# MCPEmulate0.net
KiCad netlist of a schematic drawn in Altium Designer
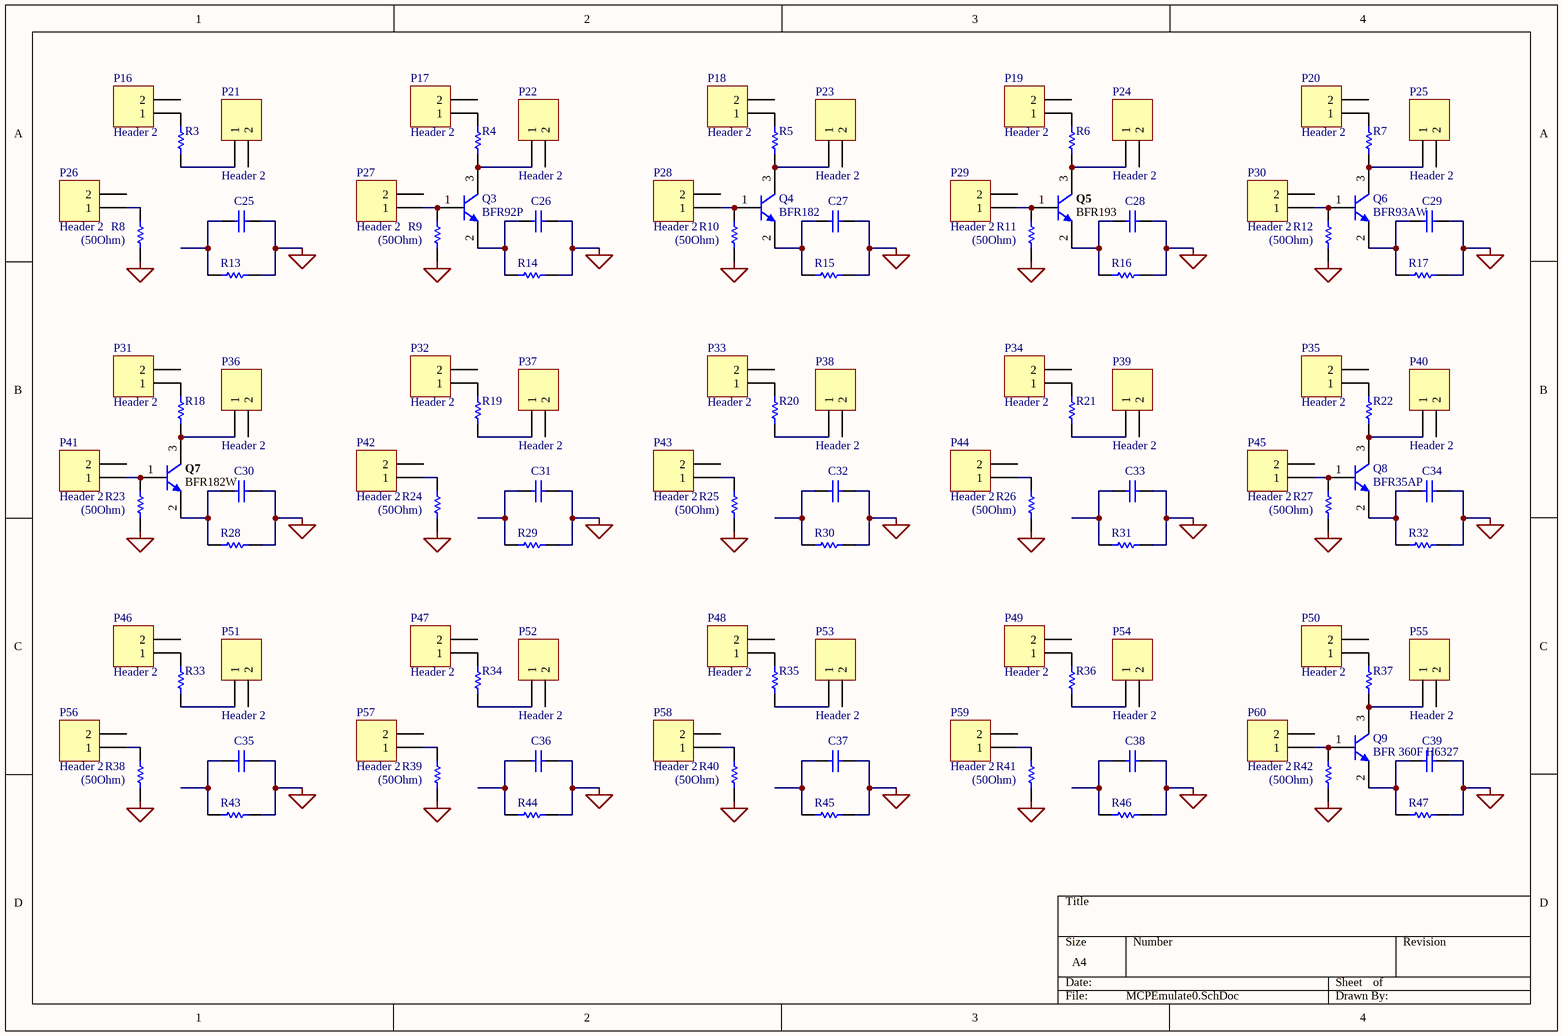
[diagram p0: MCPEmulate0.SchDoc]

(export (version "E")
  (design (tool "Eeschema 10.0.6"))
  (components
    (comp (ref "C25")
      (value "~")
      (footprint "CAPC2013X140X45NL15T25")
      (description "0402")
      (fields (field (name "PART NUMBER") "GRM21BR71A106KE51L") (field (name "MANUFACTURER") "Murata"))
      (libsource (lib "Altium Content Vault") (part "CAP"))
    )
    (comp (ref "C26")
      (value "~")
      (footprint "CAPC2013X140X45NL15T25")
      (description "0402")
      (fields (field (name "PART NUMBER") "GRM21BR71A106KE51L") (field (name "MANUFACTURER") "Murata"))
      (libsource (lib "Altium Content Vault") (part "CAP"))
    )
    (comp (ref "C27")
      (value "~")
      (footprint "CAPC2013X140X45NL15T25")
      (description "0402")
      (fields (field (name "PART NUMBER") "GRM21BR71A106KE51L") (field (name "MANUFACTURER") "Murata"))
      (libsource (lib "Altium Content Vault") (part "CAP"))
    )
    (comp (ref "C28")
      (value "~")
      (footprint "CAPC2013X140X45NL15T25")
      (description "0402")
      (fields (field (name "PART NUMBER") "GRM21BR71A106KE51L") (field (name "MANUFACTURER") "Murata"))
      (libsource (lib "Altium Content Vault") (part "CAP"))
    )
    (comp (ref "C29")
      (value "~")
      (footprint "CAPC2013X140X45NL15T25")
      (description "0402")
      (fields (field (name "PART NUMBER") "GRM21BR71A106KE51L") (field (name "MANUFACTURER") "Murata"))
      (libsource (lib "Altium Content Vault") (part "CAP"))
    )
    (comp (ref "C30")
      (value "~")
      (footprint "CAPC2013X140X45NL15T25")
      (description "0402")
      (fields (field (name "PART NUMBER") "GRM21BR71A106KE51L") (field (name "MANUFACTURER") "Murata"))
      (libsource (lib "Altium Content Vault") (part "CAP"))
    )
    (comp (ref "C31")
      (value "~")
      (footprint "CAPC2013X140X45NL15T25")
      (description "0402")
      (fields (field (name "PART NUMBER") "GRM21BR71A106KE51L") (field (name "MANUFACTURER") "Murata"))
      (libsource (lib "Altium Content Vault") (part "CAP"))
    )
    (comp (ref "C32")
      (value "~")
      (footprint "CAPC2013X140X45NL15T25")
      (description "0402")
      (fields (field (name "PART NUMBER") "GRM21BR71A106KE51L") (field (name "MANUFACTURER") "Murata"))
      (libsource (lib "Altium Content Vault") (part "CAP"))
    )
    (comp (ref "C33")
      (value "~")
      (footprint "CAPC2013X140X45NL15T25")
      (description "0402")
      (fields (field (name "PART NUMBER") "GRM21BR71A106KE51L") (field (name "MANUFACTURER") "Murata"))
      (libsource (lib "Altium Content Vault") (part "CAP"))
    )
    (comp (ref "C34")
      (value "~")
      (footprint "CAPC2013X140X45NL15T25")
      (description "0402")
      (fields (field (name "PART NUMBER") "GRM21BR71A106KE51L") (field (name "MANUFACTURER") "Murata"))
      (libsource (lib "Altium Content Vault") (part "CAP"))
    )
    (comp (ref "C35")
      (value "~")
      (footprint "CAPC2013X140X45NL15T25")
      (description "0402")
      (fields (field (name "PART NUMBER") "GRM21BR71A106KE51L") (field (name "MANUFACTURER") "Murata"))
      (libsource (lib "Altium Content Vault") (part "CAP"))
    )
    (comp (ref "C36")
      (value "~")
      (footprint "CAPC2013X140X45NL15T25")
      (description "0402")
      (fields (field (name "PART NUMBER") "GRM21BR71A106KE51L") (field (name "MANUFACTURER") "Murata"))
      (libsource (lib "Altium Content Vault") (part "CAP"))
    )
    (comp (ref "C37")
      (value "~")
      (footprint "CAPC2013X140X45NL15T25")
      (description "0402")
      (fields (field (name "PART NUMBER") "GRM21BR71A106KE51L") (field (name "MANUFACTURER") "Murata"))
      (libsource (lib "Altium Content Vault") (part "CAP"))
    )
    (comp (ref "C38")
      (value "~")
      (footprint "CAPC2013X140X45NL15T25")
      (description "0402")
      (fields (field (name "PART NUMBER") "GRM21BR71A106KE51L") (field (name "MANUFACTURER") "Murata"))
      (libsource (lib "Altium Content Vault") (part "CAP"))
    )
    (comp (ref "C39")
      (value "~")
      (footprint "CAPC2013X140X45NL15T25")
      (description "0402")
      (fields (field (name "PART NUMBER") "GRM21BR71A106KE51L") (field (name "MANUFACTURER") "Murata"))
      (libsource (lib "Altium Content Vault") (part "CAP"))
    )
    (comp (ref "P16")
      (value "Header 2")
      (footprint "HDR1X2")
      (description "Header, 2-Pin")
      (fields (field (name "PUBLISHER") "Altium Limited"))
      (libsource (lib "") (part "Header 2_1"))
    )
    (comp (ref "P17")
      (value "Header 2")
      (footprint "HDR1X2")
      (description "Header, 2-Pin")
      (fields (field (name "PUBLISHER") "Altium Limited"))
      (libsource (lib "") (part "Header 2_1"))
    )
    (comp (ref "P18")
      (value "Header 2")
      (footprint "HDR1X2")
      (description "Header, 2-Pin")
      (fields (field (name "PUBLISHER") "Altium Limited"))
      (libsource (lib "") (part "Header 2_1"))
    )
    (comp (ref "P19")
      (value "Header 2")
      (footprint "HDR1X2")
      (description "Header, 2-Pin")
      (fields (field (name "PUBLISHER") "Altium Limited"))
      (libsource (lib "") (part "Header 2_1"))
    )
    (comp (ref "P20")
      (value "Header 2")
      (footprint "HDR1X2")
      (description "Header, 2-Pin")
      (fields (field (name "PUBLISHER") "Altium Limited"))
      (libsource (lib "") (part "Header 2_1"))
    )
    (comp (ref "P21")
      (value "Header 2")
      (footprint "HDR1X2")
      (description "Header, 2-Pin")
      (fields (field (name "PUBLISHER") "Altium Limited"))
      (libsource (lib "Miscellaneous Connectors") (part "Header 2"))
    )
    (comp (ref "P22")
      (value "Header 2")
      (footprint "HDR1X2")
      (description "Header, 2-Pin")
      (fields (field (name "PUBLISHER") "Altium Limited"))
      (libsource (lib "Miscellaneous Connectors") (part "Header 2"))
    )
    (comp (ref "P23")
      (value "Header 2")
      (footprint "HDR1X2")
      (description "Header, 2-Pin")
      (fields (field (name "PUBLISHER") "Altium Limited"))
      (libsource (lib "Miscellaneous Connectors") (part "Header 2"))
    )
    (comp (ref "P24")
      (value "Header 2")
      (footprint "HDR1X2")
      (description "Header, 2-Pin")
      (fields (field (name "PUBLISHER") "Altium Limited"))
      (libsource (lib "Miscellaneous Connectors") (part "Header 2"))
    )
    (comp (ref "P25")
      (value "Header 2")
      (footprint "HDR1X2")
      (description "Header, 2-Pin")
      (fields (field (name "PUBLISHER") "Altium Limited"))
      (libsource (lib "Miscellaneous Connectors") (part "Header 2"))
    )
    (comp (ref "P26")
      (value "Header 2")
      (footprint "HDR1X2")
      (description "Header, 2-Pin")
      (fields (field (name "PUBLISHER") "Altium Limited"))
      (libsource (lib "") (part "Header 2_1"))
    )
    (comp (ref "P27")
      (value "Header 2")
      (footprint "HDR1X2")
      (description "Header, 2-Pin")
      (fields (field (name "PUBLISHER") "Altium Limited"))
      (libsource (lib "") (part "Header 2_1"))
    )
    (comp (ref "P28")
      (value "Header 2")
      (footprint "HDR1X2")
      (description "Header, 2-Pin")
      (fields (field (name "PUBLISHER") "Altium Limited"))
      (libsource (lib "") (part "Header 2_1"))
    )
    (comp (ref "P29")
      (value "Header 2")
      (footprint "HDR1X2")
      (description "Header, 2-Pin")
      (fields (field (name "PUBLISHER") "Altium Limited"))
      (libsource (lib "") (part "Header 2_1"))
    )
    (comp (ref "P30")
      (value "Header 2")
      (footprint "HDR1X2")
      (description "Header, 2-Pin")
      (fields (field (name "PUBLISHER") "Altium Limited"))
      (libsource (lib "") (part "Header 2_1"))
    )
    (comp (ref "P31")
      (value "Header 2")
      (footprint "HDR1X2")
      (description "Header, 2-Pin")
      (fields (field (name "PUBLISHER") "Altium Limited"))
      (libsource (lib "") (part "Header 2_1"))
    )
    (comp (ref "P32")
      (value "Header 2")
      (footprint "HDR1X2")
      (description "Header, 2-Pin")
      (fields (field (name "PUBLISHER") "Altium Limited"))
      (libsource (lib "") (part "Header 2_1"))
    )
    (comp (ref "P33")
      (value "Header 2")
      (footprint "HDR1X2")
      (description "Header, 2-Pin")
      (fields (field (name "PUBLISHER") "Altium Limited"))
      (libsource (lib "") (part "Header 2_1"))
    )
    (comp (ref "P34")
      (value "Header 2")
      (footprint "HDR1X2")
      (description "Header, 2-Pin")
      (fields (field (name "PUBLISHER") "Altium Limited"))
      (libsource (lib "") (part "Header 2_1"))
    )
    (comp (ref "P35")
      (value "Header 2")
      (footprint "HDR1X2")
      (description "Header, 2-Pin")
      (fields (field (name "PUBLISHER") "Altium Limited"))
      (libsource (lib "") (part "Header 2_1"))
    )
    (comp (ref "P36")
      (value "Header 2")
      (footprint "HDR1X2")
      (description "Header, 2-Pin")
      (fields (field (name "PUBLISHER") "Altium Limited"))
      (libsource (lib "Miscellaneous Connectors") (part "Header 2"))
    )
    (comp (ref "P37")
      (value "Header 2")
      (footprint "HDR1X2")
      (description "Header, 2-Pin")
      (fields (field (name "PUBLISHER") "Altium Limited"))
      (libsource (lib "Miscellaneous Connectors") (part "Header 2"))
    )
    (comp (ref "P38")
      (value "Header 2")
      (footprint "HDR1X2")
      (description "Header, 2-Pin")
      (fields (field (name "PUBLISHER") "Altium Limited"))
      (libsource (lib "Miscellaneous Connectors") (part "Header 2"))
    )
    (comp (ref "P39")
      (value "Header 2")
      (footprint "HDR1X2")
      (description "Header, 2-Pin")
      (fields (field (name "PUBLISHER") "Altium Limited"))
      (libsource (lib "Miscellaneous Connectors") (part "Header 2"))
    )
    (comp (ref "P40")
      (value "Header 2")
      (footprint "HDR1X2")
      (description "Header, 2-Pin")
      (fields (field (name "PUBLISHER") "Altium Limited"))
      (libsource (lib "Miscellaneous Connectors") (part "Header 2"))
    )
    (comp (ref "P41")
      (value "Header 2")
      (footprint "HDR1X2")
      (description "Header, 2-Pin")
      (fields (field (name "PUBLISHER") "Altium Limited"))
      (libsource (lib "") (part "Header 2_1"))
    )
    (comp (ref "P42")
      (value "Header 2")
      (footprint "HDR1X2")
      (description "Header, 2-Pin")
      (fields (field (name "PUBLISHER") "Altium Limited"))
      (libsource (lib "") (part "Header 2_1"))
    )
    (comp (ref "P43")
      (value "Header 2")
      (footprint "HDR1X2")
      (description "Header, 2-Pin")
      (fields (field (name "PUBLISHER") "Altium Limited"))
      (libsource (lib "") (part "Header 2_1"))
    )
    (comp (ref "P44")
      (value "Header 2")
      (footprint "HDR1X2")
      (description "Header, 2-Pin")
      (fields (field (name "PUBLISHER") "Altium Limited"))
      (libsource (lib "") (part "Header 2_1"))
    )
    (comp (ref "P45")
      (value "Header 2")
      (footprint "HDR1X2")
      (description "Header, 2-Pin")
      (fields (field (name "PUBLISHER") "Altium Limited"))
      (libsource (lib "") (part "Header 2_1"))
    )
    (comp (ref "P46")
      (value "Header 2")
      (footprint "HDR1X2")
      (description "Header, 2-Pin")
      (fields (field (name "PUBLISHER") "Altium Limited"))
      (libsource (lib "") (part "Header 2_1"))
    )
    (comp (ref "P47")
      (value "Header 2")
      (footprint "HDR1X2")
      (description "Header, 2-Pin")
      (fields (field (name "PUBLISHER") "Altium Limited"))
      (libsource (lib "") (part "Header 2_1"))
    )
    (comp (ref "P48")
      (value "Header 2")
      (footprint "HDR1X2")
      (description "Header, 2-Pin")
      (fields (field (name "PUBLISHER") "Altium Limited"))
      (libsource (lib "") (part "Header 2_1"))
    )
    (comp (ref "P49")
      (value "Header 2")
      (footprint "HDR1X2")
      (description "Header, 2-Pin")
      (fields (field (name "PUBLISHER") "Altium Limited"))
      (libsource (lib "") (part "Header 2_1"))
    )
    (comp (ref "P50")
      (value "Header 2")
      (footprint "HDR1X2")
      (description "Header, 2-Pin")
      (fields (field (name "PUBLISHER") "Altium Limited"))
      (libsource (lib "") (part "Header 2_1"))
    )
    (comp (ref "P51")
      (value "Header 2")
      (footprint "HDR1X2")
      (description "Header, 2-Pin")
      (fields (field (name "PUBLISHER") "Altium Limited"))
      (libsource (lib "Miscellaneous Connectors") (part "Header 2"))
    )
    (comp (ref "P52")
      (value "Header 2")
      (footprint "HDR1X2")
      (description "Header, 2-Pin")
      (fields (field (name "PUBLISHER") "Altium Limited"))
      (libsource (lib "Miscellaneous Connectors") (part "Header 2"))
    )
    (comp (ref "P53")
      (value "Header 2")
      (footprint "HDR1X2")
      (description "Header, 2-Pin")
      (fields (field (name "PUBLISHER") "Altium Limited"))
      (libsource (lib "Miscellaneous Connectors") (part "Header 2"))
    )
    (comp (ref "P54")
      (value "Header 2")
      (footprint "HDR1X2")
      (description "Header, 2-Pin")
      (fields (field (name "PUBLISHER") "Altium Limited"))
      (libsource (lib "Miscellaneous Connectors") (part "Header 2"))
    )
    (comp (ref "P55")
      (value "Header 2")
      (footprint "HDR1X2")
      (description "Header, 2-Pin")
      (fields (field (name "PUBLISHER") "Altium Limited"))
      (libsource (lib "Miscellaneous Connectors") (part "Header 2"))
    )
    (comp (ref "P56")
      (value "Header 2")
      (footprint "HDR1X2")
      (description "Header, 2-Pin")
      (fields (field (name "PUBLISHER") "Altium Limited"))
      (libsource (lib "") (part "Header 2_1"))
    )
    (comp (ref "P57")
      (value "Header 2")
      (footprint "HDR1X2")
      (description "Header, 2-Pin")
      (fields (field (name "PUBLISHER") "Altium Limited"))
      (libsource (lib "") (part "Header 2_1"))
    )
    (comp (ref "P58")
      (value "Header 2")
      (footprint "HDR1X2")
      (description "Header, 2-Pin")
      (fields (field (name "PUBLISHER") "Altium Limited"))
      (libsource (lib "") (part "Header 2_1"))
    )
    (comp (ref "P59")
      (value "Header 2")
      (footprint "HDR1X2")
      (description "Header, 2-Pin")
      (fields (field (name "PUBLISHER") "Altium Limited"))
      (libsource (lib "") (part "Header 2_1"))
    )
    (comp (ref "P60")
      (value "Header 2")
      (footprint "HDR1X2")
      (description "Header, 2-Pin")
      (fields (field (name "PUBLISHER") "Altium Limited"))
      (libsource (lib "") (part "Header 2_1"))
    )
    (comp (ref "Q3")
      (value "BFR92P")
      (footprint "INF-SOT23_N")
      (description "NPN Silicon RF Transistor, 15 V VCEO, 45 mA IC, 16 dB Gmax, SOT23, Green")
      (fields (field (name "MANUFACTURER") "Infineon"))
      (libsource (lib "Altium Content Vault") (part "INF-BFR92P-3"))
    )
    (comp (ref "Q4")
      (value "BFR182")
      (footprint "INF-SOT23_M")
      (description "NPN Silicon RF Transistor, 12 V VCEO, 35 mA IC, 18 dB Gmax, SOT23, Green")
      (fields (field (name "MANUFACTURER") "Infineon"))
      (libsource (lib "Altium Content Vault") (part "INF-BFR182-3"))
    )
    (comp (ref "Q5")
      (value "BFR193")
      (footprint "INF-SOT23_N")
      (description "NPN Silicon RF Transistor, 12 V VCEO, 80 mA IC, 15 dB Gmax, SOT23, Green")
      (fields (field (name "MANUFACTURER") "Infineon"))
      (libsource (lib "Altium Content Vault") (part "INF-BFR193-3"))
    )
    (comp (ref "Q6")
      (value "BFR93AW")
      (footprint "INF-SOT323_M")
      (description "NPN Silicon RF Transistor, 12 V VCEO, 90 mA IC, 15.5 dB Gmax, SOT323, Green")
      (fields (field (name "MANUFACTURER") "Infineon"))
      (libsource (lib "Altium Content Vault") (part "INF-BFR93AW-3"))
    )
    (comp (ref "Q7")
      (value "BFR182W")
      (footprint "INF-SOT323_L")
      (description "NPN Silicon RF Transistor, 12 V VCEO, 35 mA IC, 19 dB Gmax, SOT323, Green")
      (fields (field (name "MANUFACTURER") "Infineon"))
      (libsource (lib "Altium Content Vault") (part "INF-BFR182W-3"))
    )
    (comp (ref "Q8")
      (value "BFR35AP")
      (footprint "INF-SOT23_L")
      (description "NPN Silicon RF Transistor, 15 V VCEO, 45 mA IC, 16 dB Gmax, SOT23, Green")
      (fields (field (name "MANUFACTURER") "Infineon"))
      (libsource (lib "Altium Content Vault") (part "INF-BFR35AP-3"))
    )
    (comp (ref "Q9")
      (value "BFR 360F H6327")
      (footprint "INF-PG-TSFP-3-1_V")
      (description "Low Noise Silicon Bipolar RF Transistor, 9 V, 3-Pin TSFP, RoHS, Tape and Reel")
      (fields (field (name "MANUFACTURER") "Infineon"))
      (libsource (lib "Altium Content Vault") (part "BJT-NPN-BEC-3"))
    )
    (comp (ref "R3")
      (value "~")
      (footprint "RESC1005X40X25NL05T10")
      (description "0402")
      (fields (field (name "PART NUMBER") "RC0402FR-071KL") (field (name "MANUFACTURER") "Yageo / Phycomp"))
      (libsource (lib "Altium Content Vault") (part "RES"))
    )
    (comp (ref "R4")
      (value "~")
      (footprint "RESC1005X40X25NL05T10")
      (description "0402")
      (fields (field (name "PART NUMBER") "RC0402FR-071KL") (field (name "MANUFACTURER") "Yageo / Phycomp"))
      (libsource (lib "Altium Content Vault") (part "RES"))
    )
    (comp (ref "R5")
      (value "~")
      (footprint "RESC1005X40X25NL05T10")
      (description "0402")
      (fields (field (name "PART NUMBER") "RC0402FR-071KL") (field (name "MANUFACTURER") "Yageo / Phycomp"))
      (libsource (lib "Altium Content Vault") (part "RES"))
    )
    (comp (ref "R6")
      (value "~")
      (footprint "RESC1005X40X25NL05T10")
      (description "0402")
      (fields (field (name "PART NUMBER") "RC0402FR-071KL") (field (name "MANUFACTURER") "Yageo / Phycomp"))
      (libsource (lib "Altium Content Vault") (part "RES"))
    )
    (comp (ref "R7")
      (value "~")
      (footprint "RESC1005X40X25NL05T10")
      (description "0402")
      (fields (field (name "PART NUMBER") "RC0402FR-071KL") (field (name "MANUFACTURER") "Yageo / Phycomp"))
      (libsource (lib "Altium Content Vault") (part "RES"))
    )
    (comp (ref "R8")
      (value "(50Ohm)")
      (footprint "RESC1005X40X25NL05T10")
      (description "0402")
      (fields (field (name "PART NUMBER") "RC0402FR-071KL") (field (name "MANUFACTURER") "Yageo / Phycomp"))
      (libsource (lib "Altium Content Vault") (part "RES"))
    )
    (comp (ref "R9")
      (value "(50Ohm)")
      (footprint "RESC1005X40X25NL05T10")
      (description "0402")
      (fields (field (name "PART NUMBER") "RC0402FR-071KL") (field (name "MANUFACTURER") "Yageo / Phycomp"))
      (libsource (lib "Altium Content Vault") (part "RES"))
    )
    (comp (ref "R10")
      (value "(50Ohm)")
      (footprint "RESC1005X40X25NL05T10")
      (description "0402")
      (fields (field (name "PART NUMBER") "RC0402FR-071KL") (field (name "MANUFACTURER") "Yageo / Phycomp"))
      (libsource (lib "Altium Content Vault") (part "RES"))
    )
    (comp (ref "R11")
      (value "(50Ohm)")
      (footprint "RESC1005X40X25NL05T10")
      (description "0402")
      (fields (field (name "PART NUMBER") "RC0402FR-071KL") (field (name "MANUFACTURER") "Yageo / Phycomp"))
      (libsource (lib "Altium Content Vault") (part "RES"))
    )
    (comp (ref "R12")
      (value "(50Ohm)")
      (footprint "RESC1005X40X25NL05T10")
      (description "0402")
      (fields (field (name "PART NUMBER") "RC0402FR-071KL") (field (name "MANUFACTURER") "Yageo / Phycomp"))
      (libsource (lib "Altium Content Vault") (part "RES"))
    )
    (comp (ref "R13")
      (value "~")
      (footprint "RESC1005X40X25NL05T10")
      (description "0402")
      (fields (field (name "PART NUMBER") "RC0402FR-071KL") (field (name "MANUFACTURER") "Yageo / Phycomp"))
      (libsource (lib "Altium Content Vault") (part "RES"))
    )
    (comp (ref "R14")
      (value "~")
      (footprint "RESC1005X40X25NL05T10")
      (description "0402")
      (fields (field (name "PART NUMBER") "RC0402FR-071KL") (field (name "MANUFACTURER") "Yageo / Phycomp"))
      (libsource (lib "Altium Content Vault") (part "RES"))
    )
    (comp (ref "R15")
      (value "~")
      (footprint "RESC1005X40X25NL05T10")
      (description "0402")
      (fields (field (name "PART NUMBER") "RC0402FR-071KL") (field (name "MANUFACTURER") "Yageo / Phycomp"))
      (libsource (lib "Altium Content Vault") (part "RES"))
    )
    (comp (ref "R16")
      (value "~")
      (footprint "RESC1005X40X25NL05T10")
      (description "0402")
      (fields (field (name "PART NUMBER") "RC0402FR-071KL") (field (name "MANUFACTURER") "Yageo / Phycomp"))
      (libsource (lib "Altium Content Vault") (part "RES"))
    )
    (comp (ref "R17")
      (value "~")
      (footprint "RESC1005X40X25NL05T10")
      (description "0402")
      (fields (field (name "PART NUMBER") "RC0402FR-071KL") (field (name "MANUFACTURER") "Yageo / Phycomp"))
      (libsource (lib "Altium Content Vault") (part "RES"))
    )
    (comp (ref "R18")
      (value "~")
      (footprint "RESC1005X40X25NL05T10")
      (description "0402")
      (fields (field (name "PART NUMBER") "RC0402FR-071KL") (field (name "MANUFACTURER") "Yageo / Phycomp"))
      (libsource (lib "Altium Content Vault") (part "RES"))
    )
    (comp (ref "R19")
      (value "~")
      (footprint "RESC1005X40X25NL05T10")
      (description "0402")
      (fields (field (name "PART NUMBER") "RC0402FR-071KL") (field (name "MANUFACTURER") "Yageo / Phycomp"))
      (libsource (lib "Altium Content Vault") (part "RES"))
    )
    (comp (ref "R20")
      (value "~")
      (footprint "RESC1005X40X25NL05T10")
      (description "0402")
      (fields (field (name "PART NUMBER") "RC0402FR-071KL") (field (name "MANUFACTURER") "Yageo / Phycomp"))
      (libsource (lib "Altium Content Vault") (part "RES"))
    )
    (comp (ref "R21")
      (value "~")
      (footprint "RESC1005X40X25NL05T10")
      (description "0402")
      (fields (field (name "PART NUMBER") "RC0402FR-071KL") (field (name "MANUFACTURER") "Yageo / Phycomp"))
      (libsource (lib "Altium Content Vault") (part "RES"))
    )
    (comp (ref "R22")
      (value "~")
      (footprint "RESC1005X40X25NL05T10")
      (description "0402")
      (fields (field (name "PART NUMBER") "RC0402FR-071KL") (field (name "MANUFACTURER") "Yageo / Phycomp"))
      (libsource (lib "Altium Content Vault") (part "RES"))
    )
    (comp (ref "R23")
      (value "(50Ohm)")
      (footprint "RESC1005X40X25NL05T10")
      (description "0402")
      (fields (field (name "PART NUMBER") "RC0402FR-071KL") (field (name "MANUFACTURER") "Yageo / Phycomp"))
      (libsource (lib "Altium Content Vault") (part "RES"))
    )
    (comp (ref "R24")
      (value "(50Ohm)")
      (footprint "RESC1005X40X25NL05T10")
      (description "0402")
      (fields (field (name "PART NUMBER") "RC0402FR-071KL") (field (name "MANUFACTURER") "Yageo / Phycomp"))
      (libsource (lib "Altium Content Vault") (part "RES"))
    )
    (comp (ref "R25")
      (value "(50Ohm)")
      (footprint "RESC1005X40X25NL05T10")
      (description "0402")
      (fields (field (name "PART NUMBER") "RC0402FR-071KL") (field (name "MANUFACTURER") "Yageo / Phycomp"))
      (libsource (lib "Altium Content Vault") (part "RES"))
    )
    (comp (ref "R26")
      (value "(50Ohm)")
      (footprint "RESC1005X40X25NL05T10")
      (description "0402")
      (fields (field (name "PART NUMBER") "RC0402FR-071KL") (field (name "MANUFACTURER") "Yageo / Phycomp"))
      (libsource (lib "Altium Content Vault") (part "RES"))
    )
    (comp (ref "R27")
      (value "(50Ohm)")
      (footprint "RESC1005X40X25NL05T10")
      (description "0402")
      (fields (field (name "PART NUMBER") "RC0402FR-071KL") (field (name "MANUFACTURER") "Yageo / Phycomp"))
      (libsource (lib "Altium Content Vault") (part "RES"))
    )
    (comp (ref "R28")
      (value "~")
      (footprint "RESC1005X40X25NL05T10")
      (description "0402")
      (fields (field (name "PART NUMBER") "RC0402FR-071KL") (field (name "MANUFACTURER") "Yageo / Phycomp"))
      (libsource (lib "Altium Content Vault") (part "RES"))
    )
    (comp (ref "R29")
      (value "~")
      (footprint "RESC1005X40X25NL05T10")
      (description "0402")
      (fields (field (name "PART NUMBER") "RC0402FR-071KL") (field (name "MANUFACTURER") "Yageo / Phycomp"))
      (libsource (lib "Altium Content Vault") (part "RES"))
    )
    (comp (ref "R30")
      (value "~")
      (footprint "RESC1005X40X25NL05T10")
      (description "0402")
      (fields (field (name "PART NUMBER") "RC0402FR-071KL") (field (name "MANUFACTURER") "Yageo / Phycomp"))
      (libsource (lib "Altium Content Vault") (part "RES"))
    )
    (comp (ref "R31")
      (value "~")
      (footprint "RESC1005X40X25NL05T10")
      (description "0402")
      (fields (field (name "PART NUMBER") "RC0402FR-071KL") (field (name "MANUFACTURER") "Yageo / Phycomp"))
      (libsource (lib "Altium Content Vault") (part "RES"))
    )
    (comp (ref "R32")
      (value "~")
      (footprint "RESC1005X40X25NL05T10")
      (description "0402")
      (fields (field (name "PART NUMBER") "RC0402FR-071KL") (field (name "MANUFACTURER") "Yageo / Phycomp"))
      (libsource (lib "Altium Content Vault") (part "RES"))
    )
    (comp (ref "R33")
      (value "~")
      (footprint "RESC1005X40X25NL05T10")
      (description "0402")
      (fields (field (name "PART NUMBER") "RC0402FR-071KL") (field (name "MANUFACTURER") "Yageo / Phycomp"))
      (libsource (lib "Altium Content Vault") (part "RES"))
    )
    (comp (ref "R34")
      (value "~")
      (footprint "RESC1005X40X25NL05T10")
      (description "0402")
      (fields (field (name "PART NUMBER") "RC0402FR-071KL") (field (name "MANUFACTURER") "Yageo / Phycomp"))
      (libsource (lib "Altium Content Vault") (part "RES"))
    )
    (comp (ref "R35")
      (value "~")
      (footprint "RESC1005X40X25NL05T10")
      (description "0402")
      (fields (field (name "PART NUMBER") "RC0402FR-071KL") (field (name "MANUFACTURER") "Yageo / Phycomp"))
      (libsource (lib "Altium Content Vault") (part "RES"))
    )
    (comp (ref "R36")
      (value "~")
      (footprint "RESC1005X40X25NL05T10")
      (description "0402")
      (fields (field (name "PART NUMBER") "RC0402FR-071KL") (field (name "MANUFACTURER") "Yageo / Phycomp"))
      (libsource (lib "Altium Content Vault") (part "RES"))
    )
    (comp (ref "R37")
      (value "~")
      (footprint "RESC1005X40X25NL05T10")
      (description "0402")
      (fields (field (name "PART NUMBER") "RC0402FR-071KL") (field (name "MANUFACTURER") "Yageo / Phycomp"))
      (libsource (lib "Altium Content Vault") (part "RES"))
    )
    (comp (ref "R38")
      (value "(50Ohm)")
      (footprint "RESC1005X40X25NL05T10")
      (description "0402")
      (fields (field (name "PART NUMBER") "RC0402FR-071KL") (field (name "MANUFACTURER") "Yageo / Phycomp"))
      (libsource (lib "Altium Content Vault") (part "RES"))
    )
    (comp (ref "R39")
      (value "(50Ohm)")
      (footprint "RESC1005X40X25NL05T10")
      (description "0402")
      (fields (field (name "PART NUMBER") "RC0402FR-071KL") (field (name "MANUFACTURER") "Yageo / Phycomp"))
      (libsource (lib "Altium Content Vault") (part "RES"))
    )
    (comp (ref "R40")
      (value "(50Ohm)")
      (footprint "RESC1005X40X25NL05T10")
      (description "0402")
      (fields (field (name "PART NUMBER") "RC0402FR-071KL") (field (name "MANUFACTURER") "Yageo / Phycomp"))
      (libsource (lib "Altium Content Vault") (part "RES"))
    )
    (comp (ref "R41")
      (value "(50Ohm)")
      (footprint "RESC1005X40X25NL05T10")
      (description "0402")
      (fields (field (name "PART NUMBER") "RC0402FR-071KL") (field (name "MANUFACTURER") "Yageo / Phycomp"))
      (libsource (lib "Altium Content Vault") (part "RES"))
    )
    (comp (ref "R42")
      (value "(50Ohm)")
      (footprint "RESC1005X40X25NL05T10")
      (description "0402")
      (fields (field (name "PART NUMBER") "RC0402FR-071KL") (field (name "MANUFACTURER") "Yageo / Phycomp"))
      (libsource (lib "Altium Content Vault") (part "RES"))
    )
    (comp (ref "R43")
      (value "~")
      (footprint "RESC1005X40X25NL05T10")
      (description "0402")
      (fields (field (name "PART NUMBER") "RC0402FR-071KL") (field (name "MANUFACTURER") "Yageo / Phycomp"))
      (libsource (lib "Altium Content Vault") (part "RES"))
    )
    (comp (ref "R44")
      (value "~")
      (footprint "RESC1005X40X25NL05T10")
      (description "0402")
      (fields (field (name "PART NUMBER") "RC0402FR-071KL") (field (name "MANUFACTURER") "Yageo / Phycomp"))
      (libsource (lib "Altium Content Vault") (part "RES"))
    )
    (comp (ref "R45")
      (value "~")
      (footprint "RESC1005X40X25NL05T10")
      (description "0402")
      (fields (field (name "PART NUMBER") "RC0402FR-071KL") (field (name "MANUFACTURER") "Yageo / Phycomp"))
      (libsource (lib "Altium Content Vault") (part "RES"))
    )
    (comp (ref "R46")
      (value "~")
      (footprint "RESC1005X40X25NL05T10")
      (description "0402")
      (fields (field (name "PART NUMBER") "RC0402FR-071KL") (field (name "MANUFACTURER") "Yageo / Phycomp"))
      (libsource (lib "Altium Content Vault") (part "RES"))
    )
    (comp (ref "R47")
      (value "~")
      (footprint "RESC1005X40X25NL05T10")
      (description "0402")
      (fields (field (name "PART NUMBER") "RC0402FR-071KL") (field (name "MANUFACTURER") "Yageo / Phycomp"))
      (libsource (lib "Altium Content Vault") (part "RES"))
    )
  )
  (nets
    (net (code "1") (name "GND") (class "Default")
      (node (ref "C25") (pin "1") (pinfunction "1_1") (pintype "passive"))
      (node (ref "C26") (pin "1") (pinfunction "1_1") (pintype "passive"))
      (node (ref "C27") (pin "1") (pinfunction "1_1") (pintype "passive"))
      (node (ref "C28") (pin "1") (pinfunction "1_1") (pintype "passive"))
      (node (ref "C29") (pin "1") (pinfunction "1_1") (pintype "passive"))
      (node (ref "C30") (pin "1") (pinfunction "1_1") (pintype "passive"))
      (node (ref "C31") (pin "1") (pinfunction "1_1") (pintype "passive"))
      (node (ref "C32") (pin "1") (pinfunction "1_1") (pintype "passive"))
      (node (ref "C33") (pin "1") (pinfunction "1_1") (pintype "passive"))
      (node (ref "C34") (pin "1") (pinfunction "1_1") (pintype "passive"))
      (node (ref "C35") (pin "1") (pinfunction "1_1") (pintype "passive"))
      (node (ref "C36") (pin "1") (pinfunction "1_1") (pintype "passive"))
      (node (ref "C37") (pin "1") (pinfunction "1_1") (pintype "passive"))
      (node (ref "C38") (pin "1") (pinfunction "1_1") (pintype "passive"))
      (node (ref "C39") (pin "1") (pinfunction "1_1") (pintype "passive"))
      (node (ref "R10") (pin "1") (pinfunction "1_1") (pintype "passive"))
      (node (ref "R11") (pin "1") (pinfunction "1_1") (pintype "passive"))
      (node (ref "R12") (pin "1") (pinfunction "1_1") (pintype "passive"))
      (node (ref "R13") (pin "1") (pinfunction "1_1") (pintype "passive"))
      (node (ref "R14") (pin "1") (pinfunction "1_1") (pintype "passive"))
      (node (ref "R15") (pin "1") (pinfunction "1_1") (pintype "passive"))
      (node (ref "R16") (pin "1") (pinfunction "1_1") (pintype "passive"))
      (node (ref "R17") (pin "1") (pinfunction "1_1") (pintype "passive"))
      (node (ref "R23") (pin "1") (pinfunction "1_1") (pintype "passive"))
      (node (ref "R24") (pin "1") (pinfunction "1_1") (pintype "passive"))
      (node (ref "R25") (pin "1") (pinfunction "1_1") (pintype "passive"))
      (node (ref "R26") (pin "1") (pinfunction "1_1") (pintype "passive"))
      (node (ref "R27") (pin "1") (pinfunction "1_1") (pintype "passive"))
      (node (ref "R28") (pin "1") (pinfunction "1_1") (pintype "passive"))
      (node (ref "R29") (pin "1") (pinfunction "1_1") (pintype "passive"))
      (node (ref "R30") (pin "1") (pinfunction "1_1") (pintype "passive"))
      (node (ref "R31") (pin "1") (pinfunction "1_1") (pintype "passive"))
      (node (ref "R32") (pin "1") (pinfunction "1_1") (pintype "passive"))
      (node (ref "R38") (pin "1") (pinfunction "1_1") (pintype "passive"))
      (node (ref "R39") (pin "1") (pinfunction "1_1") (pintype "passive"))
      (node (ref "R40") (pin "1") (pinfunction "1_1") (pintype "passive"))
      (node (ref "R41") (pin "1") (pinfunction "1_1") (pintype "passive"))
      (node (ref "R42") (pin "1") (pinfunction "1_1") (pintype "passive"))
      (node (ref "R43") (pin "1") (pinfunction "1_1") (pintype "passive"))
      (node (ref "R44") (pin "1") (pinfunction "1_1") (pintype "passive"))
      (node (ref "R45") (pin "1") (pinfunction "1_1") (pintype "passive"))
      (node (ref "R46") (pin "1") (pinfunction "1_1") (pintype "passive"))
      (node (ref "R47") (pin "1") (pinfunction "1_1") (pintype "passive"))
      (node (ref "R8") (pin "1") (pinfunction "1_1") (pintype "passive"))
      (node (ref "R9") (pin "1") (pinfunction "1_1") (pintype "passive"))
    )
    (net (code "2") (name "Net-(C25-Pad2)") (class "Default")
      (node (ref "C25") (pin "2") (pinfunction "2_2") (pintype "passive"))
      (node (ref "R13") (pin "2") (pinfunction "2_2") (pintype "passive"))
    )
    (net (code "3") (name "Net-(C31-Pad2)") (class "Default")
      (node (ref "C31") (pin "2") (pinfunction "2_2") (pintype "passive"))
      (node (ref "R29") (pin "2") (pinfunction "2_2") (pintype "passive"))
    )
    (net (code "4") (name "Net-(C32-Pad2)") (class "Default")
      (node (ref "C32") (pin "2") (pinfunction "2_2") (pintype "passive"))
      (node (ref "R30") (pin "2") (pinfunction "2_2") (pintype "passive"))
    )
    (net (code "5") (name "Net-(C33-Pad2)") (class "Default")
      (node (ref "C33") (pin "2") (pinfunction "2_2") (pintype "passive"))
      (node (ref "R31") (pin "2") (pinfunction "2_2") (pintype "passive"))
    )
    (net (code "6") (name "Net-(C35-Pad2)") (class "Default")
      (node (ref "C35") (pin "2") (pinfunction "2_2") (pintype "passive"))
      (node (ref "R43") (pin "2") (pinfunction "2_2") (pintype "passive"))
    )
    (net (code "7") (name "Net-(C36-Pad2)") (class "Default")
      (node (ref "C36") (pin "2") (pinfunction "2_2") (pintype "passive"))
      (node (ref "R44") (pin "2") (pinfunction "2_2") (pintype "passive"))
    )
    (net (code "8") (name "Net-(C37-Pad2)") (class "Default")
      (node (ref "C37") (pin "2") (pinfunction "2_2") (pintype "passive"))
      (node (ref "R45") (pin "2") (pinfunction "2_2") (pintype "passive"))
    )
    (net (code "9") (name "Net-(C38-Pad2)") (class "Default")
      (node (ref "C38") (pin "2") (pinfunction "2_2") (pintype "passive"))
      (node (ref "R46") (pin "2") (pinfunction "2_2") (pintype "passive"))
    )
    (net (code "10") (name "Net-(P16-Pad1)") (class "Default")
      (node (ref "P16") (pin "1") (pinfunction "1_1") (pintype "passive"))
      (node (ref "R3") (pin "1") (pinfunction "1_1") (pintype "passive"))
    )
    (net (code "11") (name "Net-(P17-Pad1)") (class "Default")
      (node (ref "P17") (pin "1") (pinfunction "1_1") (pintype "passive"))
      (node (ref "R4") (pin "1") (pinfunction "1_1") (pintype "passive"))
    )
    (net (code "12") (name "Net-(P18-Pad1)") (class "Default")
      (node (ref "P18") (pin "1") (pinfunction "1_1") (pintype "passive"))
      (node (ref "R5") (pin "1") (pinfunction "1_1") (pintype "passive"))
    )
    (net (code "13") (name "Net-(P19-Pad1)") (class "Default")
      (node (ref "P19") (pin "1") (pinfunction "1_1") (pintype "passive"))
      (node (ref "R6") (pin "1") (pinfunction "1_1") (pintype "passive"))
    )
    (net (code "14") (name "Net-(P20-Pad1)") (class "Default")
      (node (ref "P20") (pin "1") (pinfunction "1_1") (pintype "passive"))
      (node (ref "R7") (pin "1") (pinfunction "1_1") (pintype "passive"))
    )
    (net (code "15") (name "Net-(P21-Pad1)") (class "Default")
      (node (ref "P21") (pin "1") (pinfunction "1_1") (pintype "passive"))
      (node (ref "R3") (pin "2") (pinfunction "2_2") (pintype "passive"))
    )
    (net (code "16") (name "Net-(P26-Pad1)") (class "Default")
      (node (ref "P26") (pin "1") (pinfunction "1_1") (pintype "passive"))
      (node (ref "R8") (pin "2") (pinfunction "2_2") (pintype "passive"))
    )
    (net (code "17") (name "Net-(P31-Pad1)") (class "Default")
      (node (ref "P31") (pin "1") (pinfunction "1_1") (pintype "passive"))
      (node (ref "R18") (pin "1") (pinfunction "1_1") (pintype "passive"))
    )
    (net (code "18") (name "Net-(P32-Pad1)") (class "Default")
      (node (ref "P32") (pin "1") (pinfunction "1_1") (pintype "passive"))
      (node (ref "R19") (pin "1") (pinfunction "1_1") (pintype "passive"))
    )
    (net (code "19") (name "Net-(P33-Pad1)") (class "Default")
      (node (ref "P33") (pin "1") (pinfunction "1_1") (pintype "passive"))
      (node (ref "R20") (pin "1") (pinfunction "1_1") (pintype "passive"))
    )
    (net (code "20") (name "Net-(P34-Pad1)") (class "Default")
      (node (ref "P34") (pin "1") (pinfunction "1_1") (pintype "passive"))
      (node (ref "R21") (pin "1") (pinfunction "1_1") (pintype "passive"))
    )
    (net (code "21") (name "Net-(P35-Pad1)") (class "Default")
      (node (ref "P35") (pin "1") (pinfunction "1_1") (pintype "passive"))
      (node (ref "R22") (pin "1") (pinfunction "1_1") (pintype "passive"))
    )
    (net (code "22") (name "Net-(P37-Pad1)") (class "Default")
      (node (ref "P37") (pin "1") (pinfunction "1_1") (pintype "passive"))
      (node (ref "R19") (pin "2") (pinfunction "2_2") (pintype "passive"))
    )
    (net (code "23") (name "Net-(P38-Pad1)") (class "Default")
      (node (ref "P38") (pin "1") (pinfunction "1_1") (pintype "passive"))
      (node (ref "R20") (pin "2") (pinfunction "2_2") (pintype "passive"))
    )
    (net (code "24") (name "Net-(P39-Pad1)") (class "Default")
      (node (ref "P39") (pin "1") (pinfunction "1_1") (pintype "passive"))
      (node (ref "R21") (pin "2") (pinfunction "2_2") (pintype "passive"))
    )
    (net (code "25") (name "Net-(P42-Pad1)") (class "Default")
      (node (ref "P42") (pin "1") (pinfunction "1_1") (pintype "passive"))
      (node (ref "R24") (pin "2") (pinfunction "2_2") (pintype "passive"))
    )
    (net (code "26") (name "Net-(P43-Pad1)") (class "Default")
      (node (ref "P43") (pin "1") (pinfunction "1_1") (pintype "passive"))
      (node (ref "R25") (pin "2") (pinfunction "2_2") (pintype "passive"))
    )
    (net (code "27") (name "Net-(P44-Pad1)") (class "Default")
      (node (ref "P44") (pin "1") (pinfunction "1_1") (pintype "passive"))
      (node (ref "R26") (pin "2") (pinfunction "2_2") (pintype "passive"))
    )
    (net (code "28") (name "Net-(P46-Pad1)") (class "Default")
      (node (ref "P46") (pin "1") (pinfunction "1_1") (pintype "passive"))
      (node (ref "R33") (pin "1") (pinfunction "1_1") (pintype "passive"))
    )
    (net (code "29") (name "Net-(P47-Pad1)") (class "Default")
      (node (ref "P47") (pin "1") (pinfunction "1_1") (pintype "passive"))
      (node (ref "R34") (pin "1") (pinfunction "1_1") (pintype "passive"))
    )
    (net (code "30") (name "Net-(P48-Pad1)") (class "Default")
      (node (ref "P48") (pin "1") (pinfunction "1_1") (pintype "passive"))
      (node (ref "R35") (pin "1") (pinfunction "1_1") (pintype "passive"))
    )
    (net (code "31") (name "Net-(P49-Pad1)") (class "Default")
      (node (ref "P49") (pin "1") (pinfunction "1_1") (pintype "passive"))
      (node (ref "R36") (pin "1") (pinfunction "1_1") (pintype "passive"))
    )
    (net (code "32") (name "Net-(P50-Pad1)") (class "Default")
      (node (ref "P50") (pin "1") (pinfunction "1_1") (pintype "passive"))
      (node (ref "R37") (pin "1") (pinfunction "1_1") (pintype "passive"))
    )
    (net (code "33") (name "Net-(P51-Pad1)") (class "Default")
      (node (ref "P51") (pin "1") (pinfunction "1_1") (pintype "passive"))
      (node (ref "R33") (pin "2") (pinfunction "2_2") (pintype "passive"))
    )
    (net (code "34") (name "Net-(P52-Pad1)") (class "Default")
      (node (ref "P52") (pin "1") (pinfunction "1_1") (pintype "passive"))
      (node (ref "R34") (pin "2") (pinfunction "2_2") (pintype "passive"))
    )
    (net (code "35") (name "Net-(P53-Pad1)") (class "Default")
      (node (ref "P53") (pin "1") (pinfunction "1_1") (pintype "passive"))
      (node (ref "R35") (pin "2") (pinfunction "2_2") (pintype "passive"))
    )
    (net (code "36") (name "Net-(P54-Pad1)") (class "Default")
      (node (ref "P54") (pin "1") (pinfunction "1_1") (pintype "passive"))
      (node (ref "R36") (pin "2") (pinfunction "2_2") (pintype "passive"))
    )
    (net (code "37") (name "Net-(P56-Pad1)") (class "Default")
      (node (ref "P56") (pin "1") (pinfunction "1_1") (pintype "passive"))
      (node (ref "R38") (pin "2") (pinfunction "2_2") (pintype "passive"))
    )
    (net (code "38") (name "Net-(P57-Pad1)") (class "Default")
      (node (ref "P57") (pin "1") (pinfunction "1_1") (pintype "passive"))
      (node (ref "R39") (pin "2") (pinfunction "2_2") (pintype "passive"))
    )
    (net (code "39") (name "Net-(P58-Pad1)") (class "Default")
      (node (ref "P58") (pin "1") (pinfunction "1_1") (pintype "passive"))
      (node (ref "R40") (pin "2") (pinfunction "2_2") (pintype "passive"))
    )
    (net (code "40") (name "Net-(P59-Pad1)") (class "Default")
      (node (ref "P59") (pin "1") (pinfunction "1_1") (pintype "passive"))
      (node (ref "R41") (pin "2") (pinfunction "2_2") (pintype "passive"))
    )
    (net (code "41") (name "Net-(Q3-B)") (class "Default")
      (node (ref "P27") (pin "1") (pinfunction "1_1") (pintype "passive"))
      (node (ref "Q3") (pin "1") (pinfunction "B_1") (pintype "passive"))
      (node (ref "R9") (pin "2") (pinfunction "2_2") (pintype "passive"))
    )
    (net (code "42") (name "Net-(Q3-C)") (class "Default")
      (node (ref "P22") (pin "1") (pinfunction "1_1") (pintype "passive"))
      (node (ref "Q3") (pin "3") (pinfunction "C_3") (pintype "passive"))
      (node (ref "R4") (pin "2") (pinfunction "2_2") (pintype "passive"))
    )
    (net (code "43") (name "Net-(Q3-E)") (class "Default")
      (node (ref "C26") (pin "2") (pinfunction "2_2") (pintype "passive"))
      (node (ref "Q3") (pin "2") (pinfunction "E_2") (pintype "passive"))
      (node (ref "R14") (pin "2") (pinfunction "2_2") (pintype "passive"))
    )
    (net (code "44") (name "Net-(Q4-B)") (class "Default")
      (node (ref "P28") (pin "1") (pinfunction "1_1") (pintype "passive"))
      (node (ref "Q4") (pin "1") (pinfunction "B_1") (pintype "passive"))
      (node (ref "R10") (pin "2") (pinfunction "2_2") (pintype "passive"))
    )
    (net (code "45") (name "Net-(Q4-C)") (class "Default")
      (node (ref "P23") (pin "1") (pinfunction "1_1") (pintype "passive"))
      (node (ref "Q4") (pin "3") (pinfunction "C_3") (pintype "passive"))
      (node (ref "R5") (pin "2") (pinfunction "2_2") (pintype "passive"))
    )
    (net (code "46") (name "Net-(Q4-E)") (class "Default")
      (node (ref "C27") (pin "2") (pinfunction "2_2") (pintype "passive"))
      (node (ref "Q4") (pin "2") (pinfunction "E_2") (pintype "passive"))
      (node (ref "R15") (pin "2") (pinfunction "2_2") (pintype "passive"))
    )
    (net (code "47") (name "Net-(Q5-B)") (class "Default")
      (node (ref "P29") (pin "1") (pinfunction "1_1") (pintype "passive"))
      (node (ref "Q5") (pin "1") (pinfunction "B_1") (pintype "passive"))
      (node (ref "R11") (pin "2") (pinfunction "2_2") (pintype "passive"))
    )
    (net (code "48") (name "Net-(Q5-C)") (class "Default")
      (node (ref "P24") (pin "1") (pinfunction "1_1") (pintype "passive"))
      (node (ref "Q5") (pin "3") (pinfunction "C_3") (pintype "passive"))
      (node (ref "R6") (pin "2") (pinfunction "2_2") (pintype "passive"))
    )
    (net (code "49") (name "Net-(Q5-E)") (class "Default")
      (node (ref "C28") (pin "2") (pinfunction "2_2") (pintype "passive"))
      (node (ref "Q5") (pin "2") (pinfunction "E_2") (pintype "passive"))
      (node (ref "R16") (pin "2") (pinfunction "2_2") (pintype "passive"))
    )
    (net (code "50") (name "Net-(Q6-B)") (class "Default")
      (node (ref "P30") (pin "1") (pinfunction "1_1") (pintype "passive"))
      (node (ref "Q6") (pin "1") (pinfunction "B_1") (pintype "passive"))
      (node (ref "R12") (pin "2") (pinfunction "2_2") (pintype "passive"))
    )
    (net (code "51") (name "Net-(Q6-C)") (class "Default")
      (node (ref "P25") (pin "1") (pinfunction "1_1") (pintype "passive"))
      (node (ref "Q6") (pin "3") (pinfunction "C_3") (pintype "passive"))
      (node (ref "R7") (pin "2") (pinfunction "2_2") (pintype "passive"))
    )
    (net (code "52") (name "Net-(Q6-E)") (class "Default")
      (node (ref "C29") (pin "2") (pinfunction "2_2") (pintype "passive"))
      (node (ref "Q6") (pin "2") (pinfunction "E_2") (pintype "passive"))
      (node (ref "R17") (pin "2") (pinfunction "2_2") (pintype "passive"))
    )
    (net (code "53") (name "Net-(Q7-B)") (class "Default")
      (node (ref "P41") (pin "1") (pinfunction "1_1") (pintype "passive"))
      (node (ref "Q7") (pin "1") (pinfunction "B_1") (pintype "passive"))
      (node (ref "R23") (pin "2") (pinfunction "2_2") (pintype "passive"))
    )
    (net (code "54") (name "Net-(Q7-C)") (class "Default")
      (node (ref "P36") (pin "1") (pinfunction "1_1") (pintype "passive"))
      (node (ref "Q7") (pin "3") (pinfunction "C_3") (pintype "passive"))
      (node (ref "R18") (pin "2") (pinfunction "2_2") (pintype "passive"))
    )
    (net (code "55") (name "Net-(Q7-E)") (class "Default")
      (node (ref "C30") (pin "2") (pinfunction "2_2") (pintype "passive"))
      (node (ref "Q7") (pin "2") (pinfunction "E_2") (pintype "passive"))
      (node (ref "R28") (pin "2") (pinfunction "2_2") (pintype "passive"))
    )
    (net (code "56") (name "Net-(Q8-B)") (class "Default")
      (node (ref "P45") (pin "1") (pinfunction "1_1") (pintype "passive"))
      (node (ref "Q8") (pin "1") (pinfunction "B_1") (pintype "passive"))
      (node (ref "R27") (pin "2") (pinfunction "2_2") (pintype "passive"))
    )
    (net (code "57") (name "Net-(Q8-C)") (class "Default")
      (node (ref "P40") (pin "1") (pinfunction "1_1") (pintype "passive"))
      (node (ref "Q8") (pin "3") (pinfunction "C_3") (pintype "passive"))
      (node (ref "R22") (pin "2") (pinfunction "2_2") (pintype "passive"))
    )
    (net (code "58") (name "Net-(Q8-E)") (class "Default")
      (node (ref "C34") (pin "2") (pinfunction "2_2") (pintype "passive"))
      (node (ref "Q8") (pin "2") (pinfunction "E_2") (pintype "passive"))
      (node (ref "R32") (pin "2") (pinfunction "2_2") (pintype "passive"))
    )
    (net (code "59") (name "Net-(Q9-B)") (class "Default")
      (node (ref "P60") (pin "1") (pinfunction "1_1") (pintype "passive"))
      (node (ref "Q9") (pin "1") (pinfunction "B_1") (pintype "passive"))
      (node (ref "R42") (pin "2") (pinfunction "2_2") (pintype "passive"))
    )
    (net (code "60") (name "Net-(Q9-C)") (class "Default")
      (node (ref "P55") (pin "1") (pinfunction "1_1") (pintype "passive"))
      (node (ref "Q9") (pin "3") (pinfunction "C_3") (pintype "passive"))
      (node (ref "R37") (pin "2") (pinfunction "2_2") (pintype "passive"))
    )
    (net (code "61") (name "Net-(Q9-E)") (class "Default")
      (node (ref "C39") (pin "2") (pinfunction "2_2") (pintype "passive"))
      (node (ref "Q9") (pin "2") (pinfunction "E_2") (pintype "passive"))
      (node (ref "R47") (pin "2") (pinfunction "2_2") (pintype "passive"))
    )
    (net (code "62") (name "unconnected-(P16-Pad2)") (class "Default")
      (node (ref "P16") (pin "2") (pinfunction "2_2") (pintype "passive"))
    )
    (net (code "63") (name "unconnected-(P17-Pad2)") (class "Default")
      (node (ref "P17") (pin "2") (pinfunction "2_2") (pintype "passive"))
    )
    (net (code "64") (name "unconnected-(P18-Pad2)") (class "Default")
      (node (ref "P18") (pin "2") (pinfunction "2_2") (pintype "passive"))
    )
    (net (code "65") (name "unconnected-(P19-Pad2)") (class "Default")
      (node (ref "P19") (pin "2") (pinfunction "2_2") (pintype "passive"))
    )
    (net (code "66") (name "unconnected-(P20-Pad2)") (class "Default")
      (node (ref "P20") (pin "2") (pinfunction "2_2") (pintype "passive"))
    )
    (net (code "67") (name "unconnected-(P21-Pad2)") (class "Default")
      (node (ref "P21") (pin "2") (pinfunction "2_2") (pintype "passive"))
    )
    (net (code "68") (name "unconnected-(P22-Pad2)") (class "Default")
      (node (ref "P22") (pin "2") (pinfunction "2_2") (pintype "passive"))
    )
    (net (code "69") (name "unconnected-(P23-Pad2)") (class "Default")
      (node (ref "P23") (pin "2") (pinfunction "2_2") (pintype "passive"))
    )
    (net (code "70") (name "unconnected-(P24-Pad2)") (class "Default")
      (node (ref "P24") (pin "2") (pinfunction "2_2") (pintype "passive"))
    )
    (net (code "71") (name "unconnected-(P25-Pad2)") (class "Default")
      (node (ref "P25") (pin "2") (pinfunction "2_2") (pintype "passive"))
    )
    (net (code "72") (name "unconnected-(P26-Pad2)") (class "Default")
      (node (ref "P26") (pin "2") (pinfunction "2_2") (pintype "passive"))
    )
    (net (code "73") (name "unconnected-(P27-Pad2)") (class "Default")
      (node (ref "P27") (pin "2") (pinfunction "2_2") (pintype "passive"))
    )
    (net (code "74") (name "unconnected-(P28-Pad2)") (class "Default")
      (node (ref "P28") (pin "2") (pinfunction "2_2") (pintype "passive"))
    )
    (net (code "75") (name "unconnected-(P29-Pad2)") (class "Default")
      (node (ref "P29") (pin "2") (pinfunction "2_2") (pintype "passive"))
    )
    (net (code "76") (name "unconnected-(P30-Pad2)") (class "Default")
      (node (ref "P30") (pin "2") (pinfunction "2_2") (pintype "passive"))
    )
    (net (code "77") (name "unconnected-(P31-Pad2)") (class "Default")
      (node (ref "P31") (pin "2") (pinfunction "2_2") (pintype "passive"))
    )
    (net (code "78") (name "unconnected-(P32-Pad2)") (class "Default")
      (node (ref "P32") (pin "2") (pinfunction "2_2") (pintype "passive"))
    )
    (net (code "79") (name "unconnected-(P33-Pad2)") (class "Default")
      (node (ref "P33") (pin "2") (pinfunction "2_2") (pintype "passive"))
    )
    (net (code "80") (name "unconnected-(P34-Pad2)") (class "Default")
      (node (ref "P34") (pin "2") (pinfunction "2_2") (pintype "passive"))
    )
    (net (code "81") (name "unconnected-(P35-Pad2)") (class "Default")
      (node (ref "P35") (pin "2") (pinfunction "2_2") (pintype "passive"))
    )
    (net (code "82") (name "unconnected-(P36-Pad2)") (class "Default")
      (node (ref "P36") (pin "2") (pinfunction "2_2") (pintype "passive"))
    )
    (net (code "83") (name "unconnected-(P37-Pad2)") (class "Default")
      (node (ref "P37") (pin "2") (pinfunction "2_2") (pintype "passive"))
    )
    (net (code "84") (name "unconnected-(P38-Pad2)") (class "Default")
      (node (ref "P38") (pin "2") (pinfunction "2_2") (pintype "passive"))
    )
    (net (code "85") (name "unconnected-(P39-Pad2)") (class "Default")
      (node (ref "P39") (pin "2") (pinfunction "2_2") (pintype "passive"))
    )
    (net (code "86") (name "unconnected-(P40-Pad2)") (class "Default")
      (node (ref "P40") (pin "2") (pinfunction "2_2") (pintype "passive"))
    )
    (net (code "87") (name "unconnected-(P41-Pad2)") (class "Default")
      (node (ref "P41") (pin "2") (pinfunction "2_2") (pintype "passive"))
    )
    (net (code "88") (name "unconnected-(P42-Pad2)") (class "Default")
      (node (ref "P42") (pin "2") (pinfunction "2_2") (pintype "passive"))
    )
    (net (code "89") (name "unconnected-(P43-Pad2)") (class "Default")
      (node (ref "P43") (pin "2") (pinfunction "2_2") (pintype "passive"))
    )
    (net (code "90") (name "unconnected-(P44-Pad2)") (class "Default")
      (node (ref "P44") (pin "2") (pinfunction "2_2") (pintype "passive"))
    )
    (net (code "91") (name "unconnected-(P45-Pad2)") (class "Default")
      (node (ref "P45") (pin "2") (pinfunction "2_2") (pintype "passive"))
    )
    (net (code "92") (name "unconnected-(P46-Pad2)") (class "Default")
      (node (ref "P46") (pin "2") (pinfunction "2_2") (pintype "passive"))
    )
    (net (code "93") (name "unconnected-(P47-Pad2)") (class "Default")
      (node (ref "P47") (pin "2") (pinfunction "2_2") (pintype "passive"))
    )
    (net (code "94") (name "unconnected-(P48-Pad2)") (class "Default")
      (node (ref "P48") (pin "2") (pinfunction "2_2") (pintype "passive"))
    )
    (net (code "95") (name "unconnected-(P49-Pad2)") (class "Default")
      (node (ref "P49") (pin "2") (pinfunction "2_2") (pintype "passive"))
    )
    (net (code "96") (name "unconnected-(P50-Pad2)") (class "Default")
      (node (ref "P50") (pin "2") (pinfunction "2_2") (pintype "passive"))
    )
    (net (code "97") (name "unconnected-(P51-Pad2)") (class "Default")
      (node (ref "P51") (pin "2") (pinfunction "2_2") (pintype "passive"))
    )
    (net (code "98") (name "unconnected-(P52-Pad2)") (class "Default")
      (node (ref "P52") (pin "2") (pinfunction "2_2") (pintype "passive"))
    )
    (net (code "99") (name "unconnected-(P53-Pad2)") (class "Default")
      (node (ref "P53") (pin "2") (pinfunction "2_2") (pintype "passive"))
    )
    (net (code "100") (name "unconnected-(P54-Pad2)") (class "Default")
      (node (ref "P54") (pin "2") (pinfunction "2_2") (pintype "passive"))
    )
    (net (code "101") (name "unconnected-(P55-Pad2)") (class "Default")
      (node (ref "P55") (pin "2") (pinfunction "2_2") (pintype "passive"))
    )
    (net (code "102") (name "unconnected-(P56-Pad2)") (class "Default")
      (node (ref "P56") (pin "2") (pinfunction "2_2") (pintype "passive"))
    )
    (net (code "103") (name "unconnected-(P57-Pad2)") (class "Default")
      (node (ref "P57") (pin "2") (pinfunction "2_2") (pintype "passive"))
    )
    (net (code "104") (name "unconnected-(P58-Pad2)") (class "Default")
      (node (ref "P58") (pin "2") (pinfunction "2_2") (pintype "passive"))
    )
    (net (code "105") (name "unconnected-(P59-Pad2)") (class "Default")
      (node (ref "P59") (pin "2") (pinfunction "2_2") (pintype "passive"))
    )
    (net (code "106") (name "unconnected-(P60-Pad2)") (class "Default")
      (node (ref "P60") (pin "2") (pinfunction "2_2") (pintype "passive"))
    )
  )
)
